# Mega.net
KiCad netlist of a schematic drawn in EAGLE
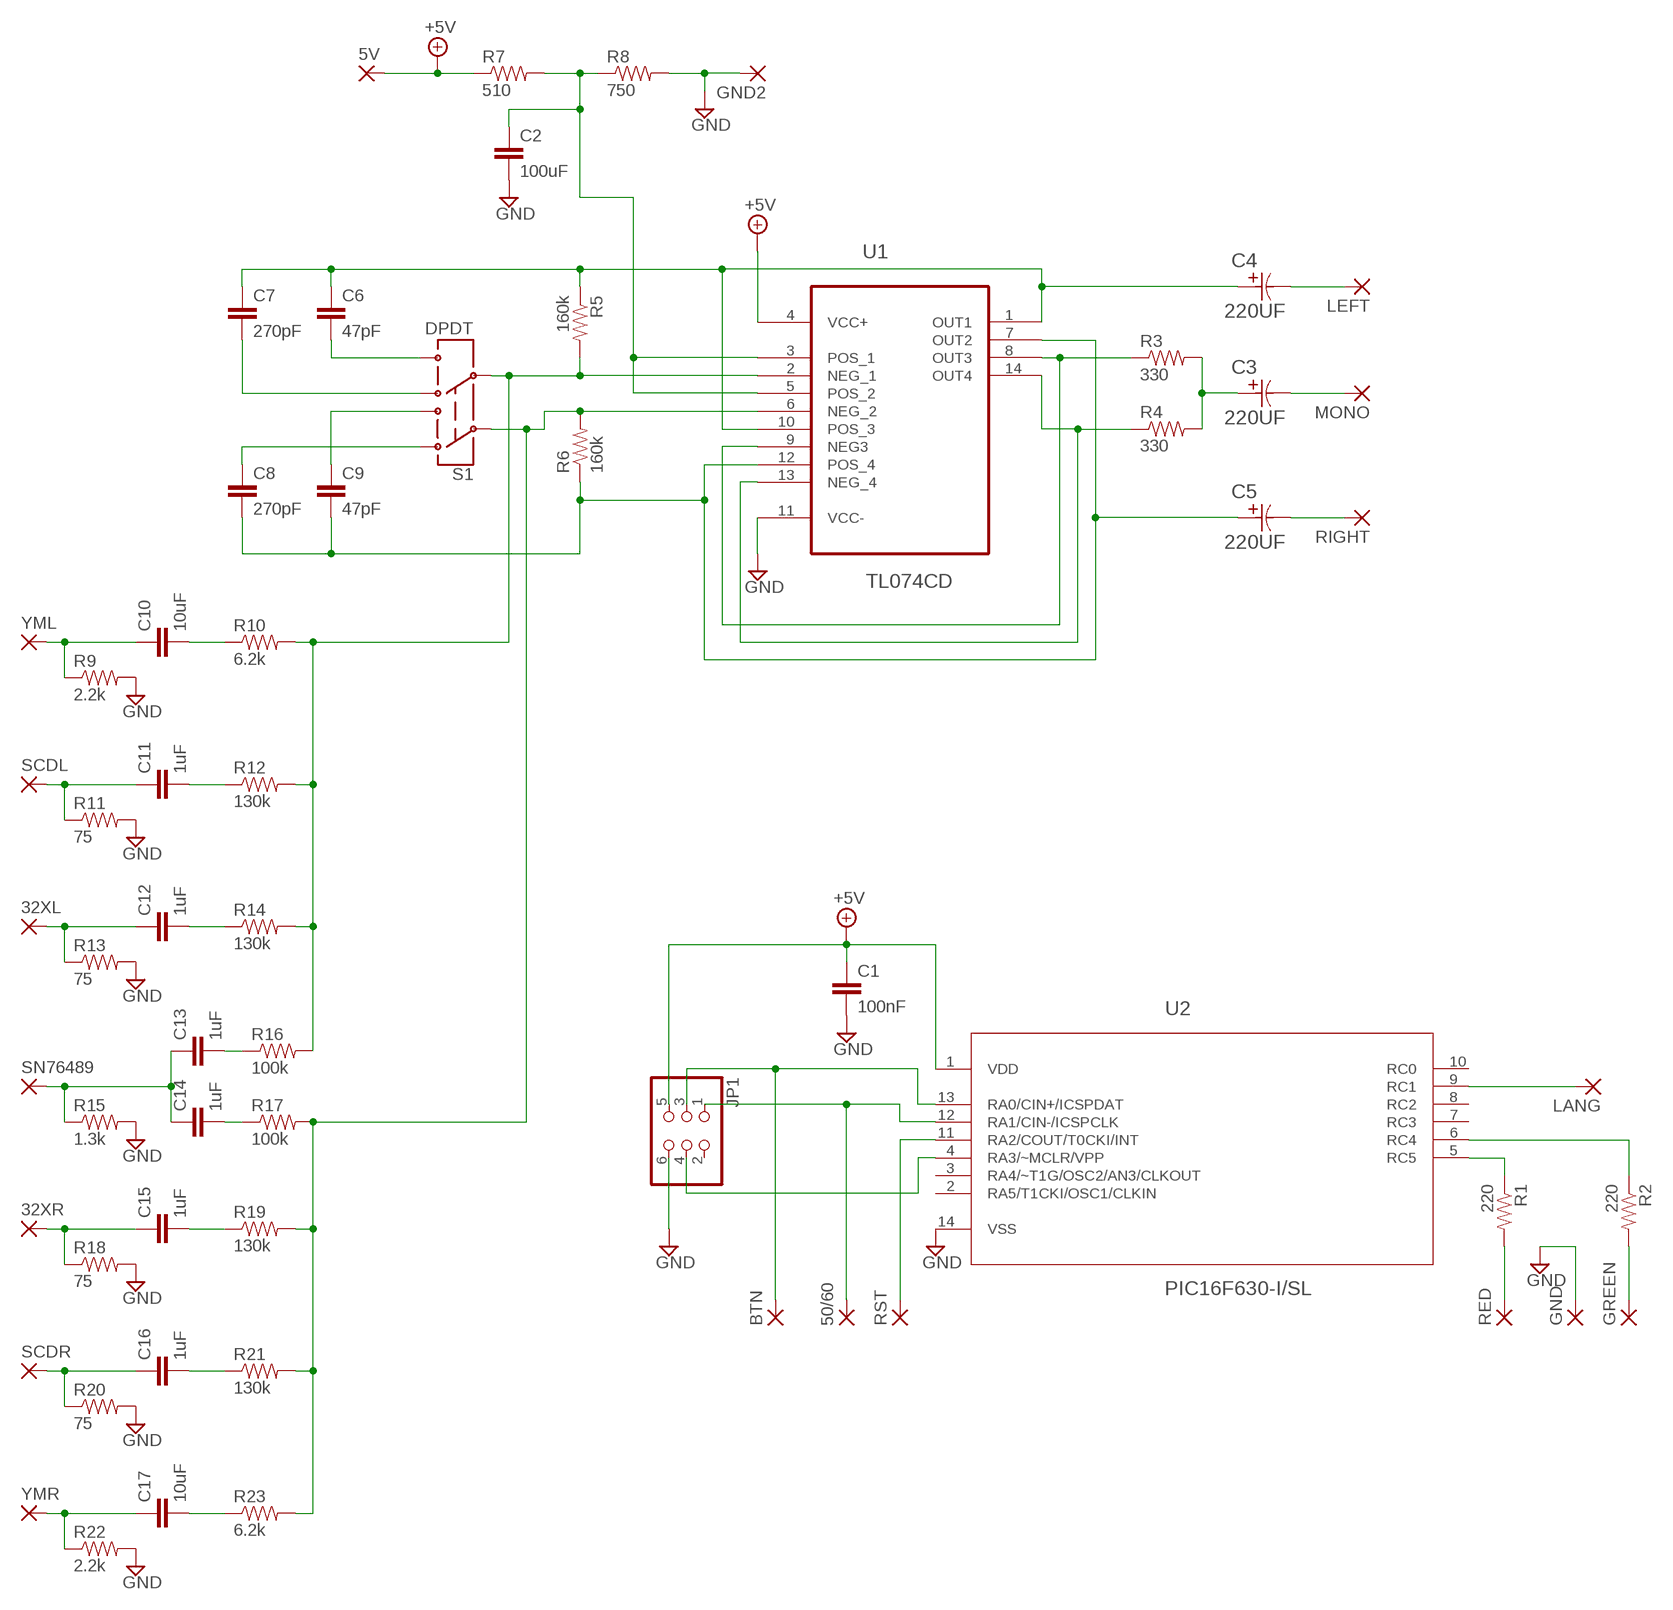
[diagram p0: schematic, sheet 1]

(export (version "E")
  (design (tool "Eeschema 10.0.6"))
  (components
    (comp (ref "5V")
      (value "SMD2")
      (footprint "eagle-import:SMD1,27-2,54")
      (libsource (lib "eagle-import") (part "SMD2"))
    )
    (comp (ref "32XL")
      (value "SMD2")
      (footprint "eagle-import:SMD1,27-2,54")
      (libsource (lib "eagle-import") (part "SMD2"))
    )
    (comp (ref "32XR")
      (value "SMD2")
      (footprint "eagle-import:SMD1,27-2,54")
      (libsource (lib "eagle-import") (part "SMD2"))
    )
    (comp (ref "50/60")
      (value "SMD2")
      (footprint "eagle-import:SMD1,27-2,54")
      (libsource (lib "eagle-import") (part "SMD2"))
    )
    (comp (ref "BTN")
      (value "SMD2")
      (footprint "eagle-import:SMD1,27-2,54")
      (libsource (lib "eagle-import") (part "SMD2"))
    )
    (comp (ref "C1")
      (value "100nF")
      (footprint "eagle-import:1206")
      (libsource (lib "eagle-import") (part "CAP1206"))
    )
    (comp (ref "C2")
      (value "100uF")
      (footprint "eagle-import:1206")
      (libsource (lib "eagle-import") (part "CAP1206"))
    )
    (comp (ref "C3")
      (value "220UF")
      (footprint "eagle-import:CAPAE830X650N")
      (fields (field (name "MPN") "EEE-FK1C221P") (field (name "TOLERANCE") "±20 %"))
      (libsource (lib "eagle-import") (part "EEE--CASE-EFK1C221P"))
    )
    (comp (ref "C4")
      (value "220UF")
      (footprint "eagle-import:CAPAE830X650N")
      (fields (field (name "MPN") "EEE-FK1C221P") (field (name "TOLERANCE") "±20 %"))
      (libsource (lib "eagle-import") (part "EEE--CASE-EFK1C221P"))
    )
    (comp (ref "C5")
      (value "220UF")
      (footprint "eagle-import:CAPAE830X650N")
      (fields (field (name "MPN") "EEE-FK1C221P") (field (name "TOLERANCE") "±20 %"))
      (libsource (lib "eagle-import") (part "EEE--CASE-EFK1C221P"))
    )
    (comp (ref "C6")
      (value "47pF")
      (footprint "eagle-import:1206")
      (libsource (lib "eagle-import") (part "CAP1206"))
    )
    (comp (ref "C7")
      (value "270pF")
      (footprint "eagle-import:1206")
      (libsource (lib "eagle-import") (part "CAP1206"))
    )
    (comp (ref "C8")
      (value "270pF")
      (footprint "eagle-import:1206")
      (libsource (lib "eagle-import") (part "CAP1206"))
    )
    (comp (ref "C9")
      (value "47pF")
      (footprint "eagle-import:1206")
      (libsource (lib "eagle-import") (part "CAP1206"))
    )
    (comp (ref "C10")
      (value "10uF")
      (footprint "eagle-import:1206")
      (libsource (lib "eagle-import") (part "CAP1206"))
    )
    (comp (ref "C11")
      (value "1uF")
      (footprint "eagle-import:1206")
      (libsource (lib "eagle-import") (part "CAP1206"))
    )
    (comp (ref "C12")
      (value "1uF")
      (footprint "eagle-import:1206")
      (libsource (lib "eagle-import") (part "CAP1206"))
    )
    (comp (ref "C13")
      (value "1uF")
      (footprint "eagle-import:1206")
      (libsource (lib "eagle-import") (part "CAP1206"))
    )
    (comp (ref "C14")
      (value "1uF")
      (footprint "eagle-import:1206")
      (libsource (lib "eagle-import") (part "CAP1206"))
    )
    (comp (ref "C15")
      (value "1uF")
      (footprint "eagle-import:1206")
      (libsource (lib "eagle-import") (part "CAP1206"))
    )
    (comp (ref "C16")
      (value "1uF")
      (footprint "eagle-import:1206")
      (libsource (lib "eagle-import") (part "CAP1206"))
    )
    (comp (ref "C17")
      (value "10uF")
      (footprint "eagle-import:1206")
      (libsource (lib "eagle-import") (part "CAP1206"))
    )
    (comp (ref "GND")
      (value "SMD2")
      (footprint "eagle-import:SMD1,27-2,54")
      (libsource (lib "eagle-import") (part "SMD2"))
    )
    (comp (ref "GND2")
      (value "SMD2")
      (footprint "eagle-import:SMD1,27-2,54")
      (libsource (lib "eagle-import") (part "SMD2"))
    )
    (comp (ref "GREEN")
      (value "SMD2")
      (footprint "eagle-import:SMD1,27-2,54")
      (libsource (lib "eagle-import") (part "SMD2"))
    )
    (comp (ref "JP1")
      (value "PINHD-2X3")
      (footprint "eagle-import:2X03")
      (libsource (lib "eagle-import") (part "PINHD-2X3"))
    )
    (comp (ref "LANG")
      (value "SMD2")
      (footprint "eagle-import:SMD1,27-2,54")
      (libsource (lib "eagle-import") (part "SMD2"))
    )
    (comp (ref "LEFT")
      (value "SMD2")
      (footprint "eagle-import:SMD1,27-2,54")
      (libsource (lib "eagle-import") (part "SMD2"))
    )
    (comp (ref "MONO")
      (value "SMD2")
      (footprint "eagle-import:SMD1,27-2,54")
      (libsource (lib "eagle-import") (part "SMD2"))
    )
    (comp (ref "R1")
      (value "220")
      (footprint "eagle-import:1206")
      (libsource (lib "eagle-import") (part "RESISTOR1206"))
    )
    (comp (ref "R2")
      (value "220")
      (footprint "eagle-import:1206")
      (libsource (lib "eagle-import") (part "RESISTOR1206"))
    )
    (comp (ref "R3")
      (value "330")
      (footprint "eagle-import:1206")
      (libsource (lib "eagle-import") (part "RESISTOR1206"))
    )
    (comp (ref "R4")
      (value "330")
      (footprint "eagle-import:1206")
      (libsource (lib "eagle-import") (part "RESISTOR1206"))
    )
    (comp (ref "R5")
      (value "160k")
      (footprint "eagle-import:1206")
      (libsource (lib "eagle-import") (part "RESISTOR1206"))
    )
    (comp (ref "R6")
      (value "160k")
      (footprint "eagle-import:1206")
      (libsource (lib "eagle-import") (part "RESISTOR1206"))
    )
    (comp (ref "R7")
      (value "510")
      (footprint "eagle-import:1206")
      (libsource (lib "eagle-import") (part "RESISTOR1206"))
    )
    (comp (ref "R8")
      (value "750")
      (footprint "eagle-import:1206")
      (libsource (lib "eagle-import") (part "RESISTOR1206"))
    )
    (comp (ref "R9")
      (value "2.2k")
      (footprint "eagle-import:1206")
      (libsource (lib "eagle-import") (part "RESISTOR1206"))
    )
    (comp (ref "R10")
      (value "6.2k")
      (footprint "eagle-import:1206")
      (libsource (lib "eagle-import") (part "RESISTOR1206"))
    )
    (comp (ref "R11")
      (value "75")
      (footprint "eagle-import:1206")
      (libsource (lib "eagle-import") (part "RESISTOR1206"))
    )
    (comp (ref "R12")
      (value "130k")
      (footprint "eagle-import:1206")
      (libsource (lib "eagle-import") (part "RESISTOR1206"))
    )
    (comp (ref "R13")
      (value "75")
      (footprint "eagle-import:1206")
      (libsource (lib "eagle-import") (part "RESISTOR1206"))
    )
    (comp (ref "R14")
      (value "130k")
      (footprint "eagle-import:1206")
      (libsource (lib "eagle-import") (part "RESISTOR1206"))
    )
    (comp (ref "R15")
      (value "1.3k")
      (footprint "eagle-import:1206")
      (libsource (lib "eagle-import") (part "RESISTOR1206"))
    )
    (comp (ref "R16")
      (value "100k")
      (footprint "eagle-import:1206")
      (libsource (lib "eagle-import") (part "RESISTOR1206"))
    )
    (comp (ref "R17")
      (value "100k")
      (footprint "eagle-import:1206")
      (libsource (lib "eagle-import") (part "RESISTOR1206"))
    )
    (comp (ref "R18")
      (value "75")
      (footprint "eagle-import:1206")
      (libsource (lib "eagle-import") (part "RESISTOR1206"))
    )
    (comp (ref "R19")
      (value "130k")
      (footprint "eagle-import:1206")
      (libsource (lib "eagle-import") (part "RESISTOR1206"))
    )
    (comp (ref "R20")
      (value "75")
      (footprint "eagle-import:1206")
      (libsource (lib "eagle-import") (part "RESISTOR1206"))
    )
    (comp (ref "R21")
      (value "130k")
      (footprint "eagle-import:1206")
      (libsource (lib "eagle-import") (part "RESISTOR1206"))
    )
    (comp (ref "R22")
      (value "2.2k")
      (footprint "eagle-import:1206")
      (libsource (lib "eagle-import") (part "RESISTOR1206"))
    )
    (comp (ref "R23")
      (value "6.2k")
      (footprint "eagle-import:1206")
      (libsource (lib "eagle-import") (part "RESISTOR1206"))
    )
    (comp (ref "RED")
      (value "SMD2")
      (footprint "eagle-import:SMD1,27-2,54")
      (libsource (lib "eagle-import") (part "SMD2"))
    )
    (comp (ref "RIGHT")
      (value "SMD2")
      (footprint "eagle-import:SMD1,27-2,54")
      (libsource (lib "eagle-import") (part "SMD2"))
    )
    (comp (ref "RST")
      (value "SMD2")
      (footprint "eagle-import:SMD1,27-2,54")
      (libsource (lib "eagle-import") (part "SMD2"))
    )
    (comp (ref "S1")
      (value "DPDT")
      (footprint "eagle-import:AYZ0202")
      (libsource (lib "eagle-import") (part "SWITCH-DPDTAYZ0202"))
    )
    (comp (ref "SCDL")
      (value "SMD2")
      (footprint "eagle-import:SMD1,27-2,54")
      (libsource (lib "eagle-import") (part "SMD2"))
    )
    (comp (ref "SCDR")
      (value "SMD2")
      (footprint "eagle-import:SMD1,27-2,54")
      (libsource (lib "eagle-import") (part "SMD2"))
    )
    (comp (ref "SN76489")
      (value "SMD2")
      (footprint "eagle-import:SMD1,27-2,54")
      (libsource (lib "eagle-import") (part "SMD2"))
    )
    (comp (ref "U1")
      (value "TL074CD")
      (footprint "eagle-import:SOIC127P600X175-14N")
      (libsource (lib "eagle-import") (part "TL074CD"))
    )
    (comp (ref "U2")
      (value "PIC16F630-I/SL")
      (footprint "eagle-import:SOIC127P600X175-14N")
      (libsource (lib "eagle-import") (part "PIC16F630-I/SL"))
    )
    (comp (ref "YML")
      (value "SMD2")
      (footprint "eagle-import:SMD1,27-2,54")
      (libsource (lib "eagle-import") (part "SMD2"))
    )
    (comp (ref "YMR")
      (value "SMD2")
      (footprint "eagle-import:SMD1,27-2,54")
      (libsource (lib "eagle-import") (part "SMD2"))
    )
  )
  (nets
    (net (code "1") (name "+5V") (class "Default")
      (node (ref "5V") (pin "1") (pinfunction "P_1") (pintype "passive"))
      (node (ref "C1") (pin "1") (pinfunction "1_1") (pintype "passive"))
      (node (ref "JP1") (pin "5") (pinfunction "5_5") (pintype "passive"))
      (node (ref "R7") (pin "1") (pinfunction "1_1") (pintype "passive"))
      (node (ref "U1") (pin "4") (pinfunction "VCC+_4") (pintype "power_in"))
      (node (ref "U2") (pin "1") (pinfunction "VDD_1") (pintype "power_in"))
    )
    (net (code "2") (name "GND") (class "Default")
      (node (ref "C1") (pin "2") (pinfunction "2_2") (pintype "passive"))
      (node (ref "C2") (pin "2") (pinfunction "2_2") (pintype "passive"))
      (node (ref "GND") (pin "1") (pinfunction "P_1") (pintype "passive"))
      (node (ref "GND2") (pin "1") (pinfunction "P_1") (pintype "passive"))
      (node (ref "JP1") (pin "6") (pinfunction "6_6") (pintype "passive"))
      (node (ref "R11") (pin "2") (pinfunction "2_2") (pintype "passive"))
      (node (ref "R13") (pin "2") (pinfunction "2_2") (pintype "passive"))
      (node (ref "R15") (pin "2") (pinfunction "2_2") (pintype "passive"))
      (node (ref "R18") (pin "2") (pinfunction "2_2") (pintype "passive"))
      (node (ref "R20") (pin "2") (pinfunction "2_2") (pintype "passive"))
      (node (ref "R22") (pin "2") (pinfunction "2_2") (pintype "passive"))
      (node (ref "R8") (pin "2") (pinfunction "2_2") (pintype "passive"))
      (node (ref "R9") (pin "2") (pinfunction "2_2") (pintype "passive"))
      (node (ref "U1") (pin "11") (pinfunction "VCC-_11") (pintype "power_in"))
      (node (ref "U2") (pin "14") (pinfunction "VSS_14") (pintype "power_in"))
    )
    (net (code "3") (name "Net-(32XL-P)") (class "Default")
      (node (ref "32XL") (pin "1") (pinfunction "P_1") (pintype "passive"))
      (node (ref "C12") (pin "1") (pinfunction "1_1") (pintype "passive"))
      (node (ref "R13") (pin "1") (pinfunction "1_1") (pintype "passive"))
    )
    (net (code "4") (name "Net-(32XR-P)") (class "Default")
      (node (ref "32XR") (pin "1") (pinfunction "P_1") (pintype "passive"))
      (node (ref "C15") (pin "1") (pinfunction "1_1") (pintype "passive"))
      (node (ref "R18") (pin "1") (pinfunction "1_1") (pintype "passive"))
    )
    (net (code "5") (name "Net-(50/60-P)") (class "Default")
      (node (ref "50/60") (pin "1") (pinfunction "P_1") (pintype "passive"))
      (node (ref "JP1") (pin "1") (pinfunction "1_1") (pintype "passive"))
      (node (ref "U2") (pin "12") (pinfunction "RA1/CIN-/ICSPCLK_12") (pintype "bidirectional"))
    )
    (net (code "6") (name "Net-(BTN-P)") (class "Default")
      (node (ref "BTN") (pin "1") (pinfunction "P_1") (pintype "passive"))
      (node (ref "JP1") (pin "3") (pinfunction "3_3") (pintype "passive"))
      (node (ref "U2") (pin "13") (pinfunction "RA0/CIN+/ICSPDAT_13") (pintype "bidirectional"))
    )
    (net (code "7") (name "Net-(C3-Pad1)") (class "Default")
      (node (ref "C3") (pin "1") (pinfunction "1_1") (pintype "passive"))
      (node (ref "R3") (pin "2") (pinfunction "2_2") (pintype "passive"))
      (node (ref "R4") (pin "2") (pinfunction "2_2") (pintype "passive"))
    )
    (net (code "8") (name "Net-(C6-Pad2)") (class "Default")
      (node (ref "C6") (pin "2") (pinfunction "2_2") (pintype "passive"))
      (node (ref "S1") (pin "6") (pinfunction "6_6") (pintype "bidirectional"))
    )
    (net (code "9") (name "Net-(C7-Pad2)") (class "Default")
      (node (ref "C7") (pin "2") (pinfunction "2_2") (pintype "passive"))
      (node (ref "S1") (pin "4") (pinfunction "4_4") (pintype "bidirectional"))
    )
    (net (code "10") (name "Net-(C8-Pad1)") (class "Default")
      (node (ref "C8") (pin "1") (pinfunction "1_1") (pintype "passive"))
      (node (ref "S1") (pin "1") (pinfunction "1_1") (pintype "bidirectional"))
    )
    (net (code "11") (name "Net-(C9-Pad1)") (class "Default")
      (node (ref "C9") (pin "1") (pinfunction "1_1") (pintype "passive"))
      (node (ref "S1") (pin "3") (pinfunction "3_3") (pintype "bidirectional"))
    )
    (net (code "12") (name "Net-(C10-Pad2)") (class "Default")
      (node (ref "C10") (pin "2") (pinfunction "2_2") (pintype "passive"))
      (node (ref "R10") (pin "1") (pinfunction "1_1") (pintype "passive"))
    )
    (net (code "13") (name "Net-(C11-Pad2)") (class "Default")
      (node (ref "C11") (pin "2") (pinfunction "2_2") (pintype "passive"))
      (node (ref "R12") (pin "1") (pinfunction "1_1") (pintype "passive"))
    )
    (net (code "14") (name "Net-(C12-Pad2)") (class "Default")
      (node (ref "C12") (pin "2") (pinfunction "2_2") (pintype "passive"))
      (node (ref "R14") (pin "1") (pinfunction "1_1") (pintype "passive"))
    )
    (net (code "15") (name "Net-(C13-Pad2)") (class "Default")
      (node (ref "C13") (pin "2") (pinfunction "2_2") (pintype "passive"))
      (node (ref "R16") (pin "1") (pinfunction "1_1") (pintype "passive"))
    )
    (net (code "16") (name "Net-(C14-Pad2)") (class "Default")
      (node (ref "C14") (pin "2") (pinfunction "2_2") (pintype "passive"))
      (node (ref "R17") (pin "1") (pinfunction "1_1") (pintype "passive"))
    )
    (net (code "17") (name "Net-(C15-Pad2)") (class "Default")
      (node (ref "C15") (pin "2") (pinfunction "2_2") (pintype "passive"))
      (node (ref "R19") (pin "1") (pinfunction "1_1") (pintype "passive"))
    )
    (net (code "18") (name "Net-(C16-Pad2)") (class "Default")
      (node (ref "C16") (pin "2") (pinfunction "2_2") (pintype "passive"))
      (node (ref "R21") (pin "1") (pinfunction "1_1") (pintype "passive"))
    )
    (net (code "19") (name "Net-(C17-Pad2)") (class "Default")
      (node (ref "C17") (pin "2") (pinfunction "2_2") (pintype "passive"))
      (node (ref "R23") (pin "1") (pinfunction "1_1") (pintype "passive"))
    )
    (net (code "20") (name "Net-(GREEN-P)") (class "Default")
      (node (ref "GREEN") (pin "1") (pinfunction "P_1") (pintype "passive"))
      (node (ref "R2") (pin "2") (pinfunction "2_2") (pintype "passive"))
    )
    (net (code "21") (name "Net-(LANG-P)") (class "Default")
      (node (ref "LANG") (pin "1") (pinfunction "P_1") (pintype "passive"))
      (node (ref "U2") (pin "9") (pinfunction "RC1_9") (pintype "bidirectional"))
    )
    (net (code "22") (name "Net-(LEFT-P)") (class "Default")
      (node (ref "C4") (pin "2") (pinfunction "2_2") (pintype "passive"))
      (node (ref "LEFT") (pin "1") (pinfunction "P_1") (pintype "passive"))
    )
    (net (code "23") (name "Net-(MONO-P)") (class "Default")
      (node (ref "C3") (pin "2") (pinfunction "2_2") (pintype "passive"))
      (node (ref "MONO") (pin "1") (pinfunction "P_1") (pintype "passive"))
    )
    (net (code "24") (name "Net-(RED-P)") (class "Default")
      (node (ref "R1") (pin "2") (pinfunction "2_2") (pintype "passive"))
      (node (ref "RED") (pin "1") (pinfunction "P_1") (pintype "passive"))
    )
    (net (code "25") (name "Net-(RIGHT-P)") (class "Default")
      (node (ref "C5") (pin "2") (pinfunction "2_2") (pintype "passive"))
      (node (ref "RIGHT") (pin "1") (pinfunction "P_1") (pintype "passive"))
    )
    (net (code "26") (name "Net-(RST-P)") (class "Default")
      (node (ref "RST") (pin "1") (pinfunction "P_1") (pintype "passive"))
      (node (ref "U2") (pin "11") (pinfunction "RA2/COUT/T0CKI/INT_11") (pintype "bidirectional"))
    )
    (net (code "27") (name "Net-(SCDL-P)") (class "Default")
      (node (ref "C11") (pin "1") (pinfunction "1_1") (pintype "passive"))
      (node (ref "R11") (pin "1") (pinfunction "1_1") (pintype "passive"))
      (node (ref "SCDL") (pin "1") (pinfunction "P_1") (pintype "passive"))
    )
    (net (code "28") (name "Net-(SCDR-P)") (class "Default")
      (node (ref "C16") (pin "1") (pinfunction "1_1") (pintype "passive"))
      (node (ref "R20") (pin "1") (pinfunction "1_1") (pintype "passive"))
      (node (ref "SCDR") (pin "1") (pinfunction "P_1") (pintype "passive"))
    )
    (net (code "29") (name "Net-(SN76489-P)") (class "Default")
      (node (ref "C13") (pin "1") (pinfunction "1_1") (pintype "passive"))
      (node (ref "C14") (pin "1") (pinfunction "1_1") (pintype "passive"))
      (node (ref "R15") (pin "1") (pinfunction "1_1") (pintype "passive"))
      (node (ref "SN76489") (pin "1") (pinfunction "P_1") (pintype "passive"))
    )
    (net (code "30") (name "Net-(U1-NEG3)") (class "Default")
      (node (ref "R3") (pin "1") (pinfunction "1_1") (pintype "passive"))
      (node (ref "U1") (pin "8") (pinfunction "OUT3_8") (pintype "output"))
      (node (ref "U1") (pin "9") (pinfunction "NEG3_9") (pintype "input"))
    )
    (net (code "31") (name "Net-(U1-NEG_1)") (class "Default")
      (node (ref "R10") (pin "2") (pinfunction "2_2") (pintype "passive"))
      (node (ref "R12") (pin "2") (pinfunction "2_2") (pintype "passive"))
      (node (ref "R14") (pin "2") (pinfunction "2_2") (pintype "passive"))
      (node (ref "R16") (pin "2") (pinfunction "2_2") (pintype "passive"))
      (node (ref "R5") (pin "2") (pinfunction "2_2") (pintype "passive"))
      (node (ref "S1") (pin "5") (pinfunction "5_5") (pintype "bidirectional"))
      (node (ref "U1") (pin "2") (pinfunction "NEG_1_2") (pintype "input"))
    )
    (net (code "32") (name "Net-(U1-NEG_2)") (class "Default")
      (node (ref "R17") (pin "2") (pinfunction "2_2") (pintype "passive"))
      (node (ref "R19") (pin "2") (pinfunction "2_2") (pintype "passive"))
      (node (ref "R21") (pin "2") (pinfunction "2_2") (pintype "passive"))
      (node (ref "R23") (pin "2") (pinfunction "2_2") (pintype "passive"))
      (node (ref "R6") (pin "2") (pinfunction "2_2") (pintype "passive"))
      (node (ref "S1") (pin "2") (pinfunction "2_2") (pintype "bidirectional"))
      (node (ref "U1") (pin "6") (pinfunction "NEG_2_6") (pintype "input"))
    )
    (net (code "33") (name "Net-(U1-NEG_4)") (class "Default")
      (node (ref "R4") (pin "1") (pinfunction "1_1") (pintype "passive"))
      (node (ref "U1") (pin "13") (pinfunction "NEG_4_13") (pintype "input"))
      (node (ref "U1") (pin "14") (pinfunction "OUT4_14") (pintype "output"))
    )
    (net (code "34") (name "Net-(U1-OUT1)") (class "Default")
      (node (ref "C4") (pin "1") (pinfunction "1_1") (pintype "passive"))
      (node (ref "C6") (pin "1") (pinfunction "1_1") (pintype "passive"))
      (node (ref "C7") (pin "1") (pinfunction "1_1") (pintype "passive"))
      (node (ref "R5") (pin "1") (pinfunction "1_1") (pintype "passive"))
      (node (ref "U1") (pin "1") (pinfunction "OUT1_1") (pintype "output"))
      (node (ref "U1") (pin "10") (pinfunction "POS_3_10") (pintype "input"))
    )
    (net (code "35") (name "Net-(U1-OUT2)") (class "Default")
      (node (ref "C5") (pin "1") (pinfunction "1_1") (pintype "passive"))
      (node (ref "C8") (pin "2") (pinfunction "2_2") (pintype "passive"))
      (node (ref "C9") (pin "2") (pinfunction "2_2") (pintype "passive"))
      (node (ref "R6") (pin "1") (pinfunction "1_1") (pintype "passive"))
      (node (ref "U1") (pin "12") (pinfunction "POS_4_12") (pintype "input"))
      (node (ref "U1") (pin "7") (pinfunction "OUT2_7") (pintype "output"))
    )
    (net (code "36") (name "Net-(U1-POS_1)") (class "Default")
      (node (ref "C2") (pin "1") (pinfunction "1_1") (pintype "passive"))
      (node (ref "R7") (pin "2") (pinfunction "2_2") (pintype "passive"))
      (node (ref "R8") (pin "1") (pinfunction "1_1") (pintype "passive"))
      (node (ref "U1") (pin "3") (pinfunction "POS_1_3") (pintype "input"))
      (node (ref "U1") (pin "5") (pinfunction "POS_2_5") (pintype "input"))
    )
    (net (code "37") (name "Net-(U2-RA3{slash}~{MCLR{slash}VPP})") (class "Default")
      (node (ref "JP1") (pin "4") (pinfunction "4_4") (pintype "passive"))
      (node (ref "U2") (pin "4") (pinfunction "RA3/~{MCLR/VPP}_4") (pintype "bidirectional"))
    )
    (net (code "38") (name "Net-(U2-RC4)") (class "Default")
      (node (ref "R2") (pin "1") (pinfunction "1_1") (pintype "passive"))
      (node (ref "U2") (pin "6") (pinfunction "RC4_6") (pintype "bidirectional"))
    )
    (net (code "39") (name "Net-(U2-RC5)") (class "Default")
      (node (ref "R1") (pin "1") (pinfunction "1_1") (pintype "passive"))
      (node (ref "U2") (pin "5") (pinfunction "RC5_5") (pintype "bidirectional"))
    )
    (net (code "40") (name "Net-(YML-P)") (class "Default")
      (node (ref "C10") (pin "1") (pinfunction "1_1") (pintype "passive"))
      (node (ref "R9") (pin "1") (pinfunction "1_1") (pintype "passive"))
      (node (ref "YML") (pin "1") (pinfunction "P_1") (pintype "passive"))
    )
    (net (code "41") (name "Net-(YMR-P)") (class "Default")
      (node (ref "C17") (pin "1") (pinfunction "1_1") (pintype "passive"))
      (node (ref "R22") (pin "1") (pinfunction "1_1") (pintype "passive"))
      (node (ref "YMR") (pin "1") (pinfunction "P_1") (pintype "passive"))
    )
    (net (code "42") (name "unconnected-(JP1-Pad2)") (class "Default")
      (node (ref "JP1") (pin "2") (pinfunction "2_2") (pintype "passive"))
    )
    (net (code "43") (name "unconnected-(U2-RA4{slash}~{T1G{slash}OSC2{slash}AN3{slash}CLKOUT}-Pad3)") (class "Default")
      (node (ref "U2") (pin "3") (pinfunction "RA4/~{T1G/OSC2/AN3/CLKOUT}_3") (pintype "bidirectional"))
    )
    (net (code "44") (name "unconnected-(U2-RA5{slash}T1CKI{slash}OSC1{slash}CLKIN-Pad2)") (class "Default")
      (node (ref "U2") (pin "2") (pinfunction "RA5/T1CKI/OSC1/CLKIN_2") (pintype "bidirectional"))
    )
    (net (code "45") (name "unconnected-(U2-RC0-Pad10)") (class "Default")
      (node (ref "U2") (pin "10") (pinfunction "RC0_10") (pintype "bidirectional"))
    )
    (net (code "46") (name "unconnected-(U2-RC2-Pad8)") (class "Default")
      (node (ref "U2") (pin "8") (pinfunction "RC2_8") (pintype "bidirectional"))
    )
    (net (code "47") (name "unconnected-(U2-RC3-Pad7)") (class "Default")
      (node (ref "U2") (pin "7") (pinfunction "RC3_7") (pintype "bidirectional"))
    )
  )
)
